# FrontPanelConnector.net
KiCad netlist of a schematic drawn in Altium Designer
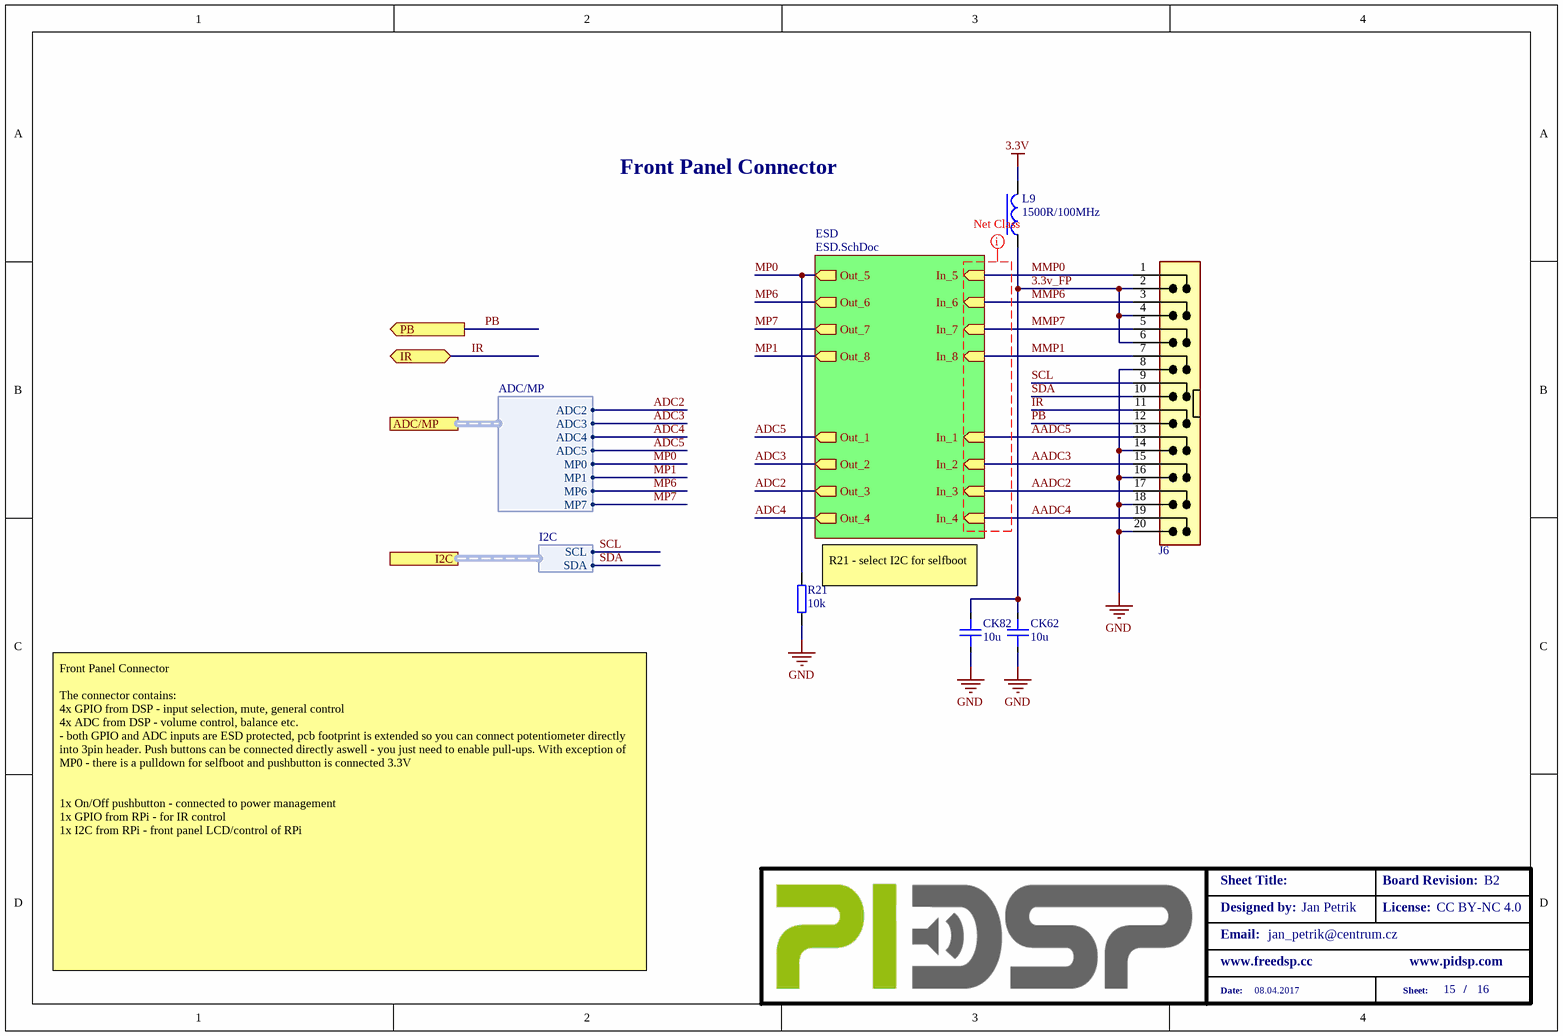
[diagram p0: FrontPanelConnector.SchDoc]

(export (version "E")
  (design (tool "Eeschema 10.0.6"))
  (components
    (comp (ref "CK62")
      (value "10u")
      (footprint "CAPC3216X12N(SMC1206)")
      (description "MLCC")
      (fields
        (field (name "TOLERANCE") "10%")
        (field (name "VOLTAGE") "50")
        (field (name "AUTHOR") "JP/10.06.2014")
      )
      (libsource (lib "JP_C") (part "10u-50V-1206-X5R"))
    )
    (comp (ref "CK82")
      (value "10u")
      (footprint "CAPC3216X12N(SMC1206)")
      (description "MLCC")
      (fields
        (field (name "TOLERANCE") "10%")
        (field (name "VOLTAGE") "50")
        (field (name "AUTHOR") "JP/10.06.2014")
      )
      (libsource (lib "JP_C") (part "10u-50V-1206-X5R"))
    )
    (comp (ref "J6") (value "MLW 2x10") (footprint "MLW20G_BG") (libsource (lib "JP_CONN") (part "MLW 2x10")))
    (comp (ref "L9")
      (value "1500R/100MHz")
      (footprint "INDC2012X08N(SML0805)")
      (description "Multilayer SMD Ferrite 1500R/100MHz")
      (fields (field (name "AUTHOR") "JP/05.06.2014"))
      (libsource (lib "JP_L") (part "MMZ2012Y152B"))
    )
    (comp (ref "R21")
      (value "10k")
      (footprint "RESC1608X06N(SMR0603)")
      (description "Chip Resistor")
      (fields (field (name "AUTHOR") "JP/10.06.2014"))
      (libsource (lib "JP_R") (part "10k-100mW-0603-ThickFilm"))
    )
  )
  (nets
    (net (code "3") (name "/3.3v_FP") (class "Default")
      (node (ref "CK62") (pin "1") (pinfunction "1_1") (pintype "passive"))
      (node (ref "CK82") (pin "1") (pinfunction "1_1") (pintype "passive"))
      (node (ref "J6") (pin "2") (pinfunction "2_2") (pintype "passive"))
      (node (ref "J6") (pin "4") (pinfunction "4_4") (pintype "passive"))
      (node (ref "J6") (pin "6") (pinfunction "6_6") (pintype "passive"))
      (node (ref "L9") (pin "1") (pintype "passive"))
    )
    (net (code "4") (name "/AADC2") (class "Default")
      (node (ref "J6") (pin "17") (pinfunction "17_17") (pintype "passive"))
    )
    (net (code "5") (name "/AADC3") (class "Default")
      (node (ref "J6") (pin "15") (pinfunction "15_15") (pintype "passive"))
    )
    (net (code "6") (name "/AADC4") (class "Default")
      (node (ref "J6") (pin "19") (pinfunction "19_19") (pintype "passive"))
    )
    (net (code "7") (name "/AADC5") (class "Default")
      (node (ref "J6") (pin "13") (pinfunction "13_13") (pintype "passive"))
    )
    (net (code "12") (name "/IR") (class "Default")
      (node (ref "J6") (pin "11") (pinfunction "11_11") (pintype "passive"))
    )
    (net (code "13") (name "/MMP0") (class "Default")
      (node (ref "J6") (pin "1") (pinfunction "1_1") (pintype "passive"))
    )
    (net (code "14") (name "/MMP1") (class "Default")
      (node (ref "J6") (pin "7") (pinfunction "7_7") (pintype "passive"))
    )
    (net (code "15") (name "/MMP6") (class "Default")
      (node (ref "J6") (pin "3") (pinfunction "3_3") (pintype "passive"))
    )
    (net (code "16") (name "/MMP7") (class "Default")
      (node (ref "J6") (pin "5") (pinfunction "5_5") (pintype "passive"))
    )
    (net (code "17") (name "/MP0") (class "Default")
      (node (ref "R21") (pin "2") (pinfunction "2_2") (pintype "passive"))
    )
    (net (code "21") (name "/PB") (class "Default")
      (node (ref "J6") (pin "12") (pinfunction "12_12") (pintype "passive"))
    )
    (net (code "22") (name "/SCL") (class "Default")
      (node (ref "J6") (pin "9") (pinfunction "9_9") (pintype "passive"))
    )
    (net (code "23") (name "/SDA") (class "Default")
      (node (ref "J6") (pin "10") (pinfunction "10_10") (pintype "passive"))
    )
    (net (code "26") (name "3.3V") (class "Default") (node (ref "L9") (pin "2") (pintype "passive")))
    (net (code "27") (name "GND") (class "Default")
      (node (ref "CK62") (pin "2") (pinfunction "2_2") (pintype "passive"))
      (node (ref "CK82") (pin "2") (pinfunction "2_2") (pintype "passive"))
      (node (ref "J6") (pin "14") (pinfunction "14_14") (pintype "passive"))
      (node (ref "J6") (pin "16") (pinfunction "16_16") (pintype "passive"))
      (node (ref "J6") (pin "18") (pinfunction "18_18") (pintype "passive"))
      (node (ref "J6") (pin "20") (pinfunction "20_20") (pintype "passive"))
      (node (ref "J6") (pin "8") (pinfunction "8_8") (pintype "passive"))
      (node (ref "R21") (pin "1") (pinfunction "1_1") (pintype "passive"))
    )
  )
)
